# lightMiner.net
KiCad netlist of a schematic drawn in EAGLE
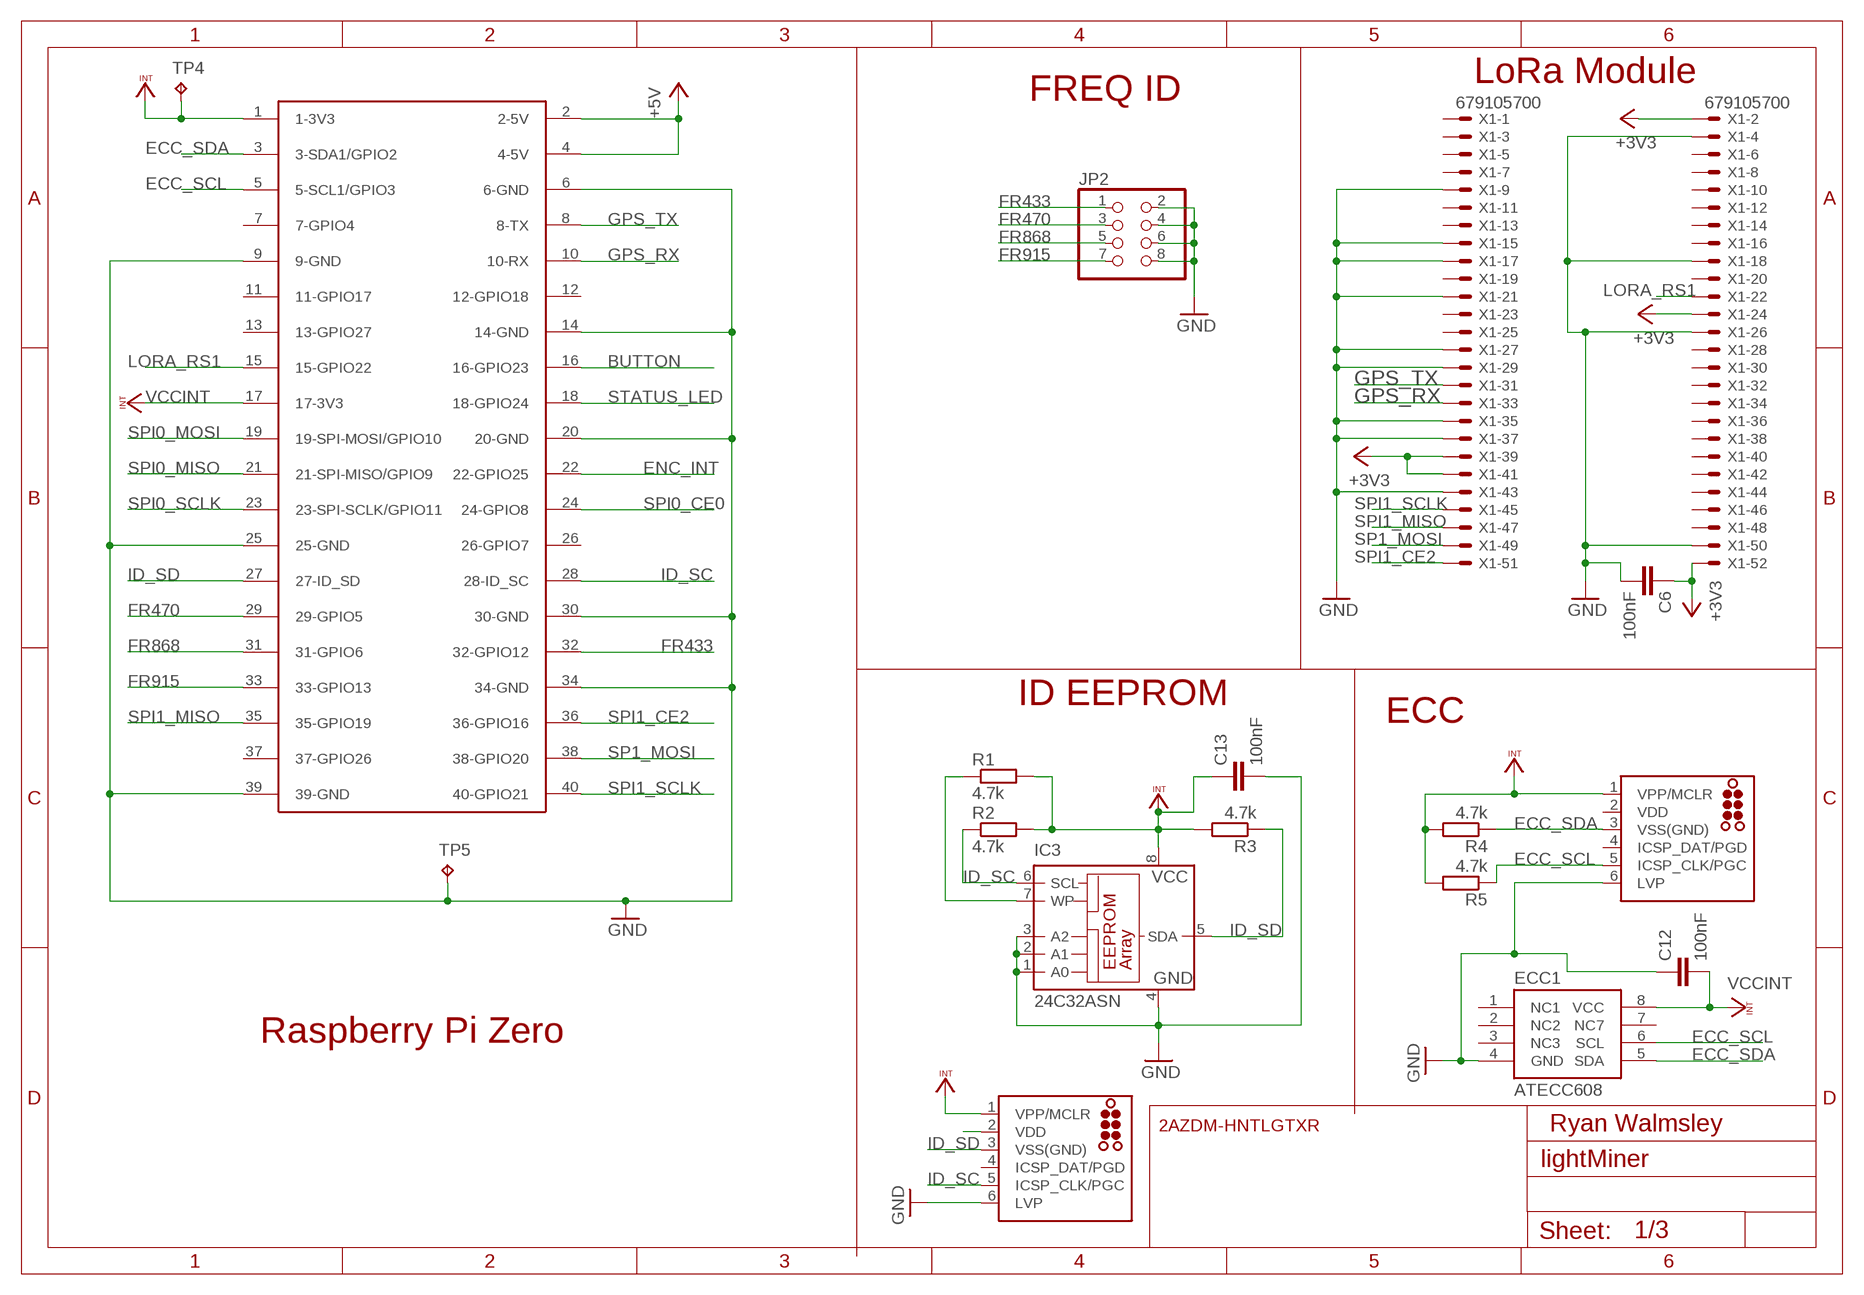
[diagram p0: schematic, sheet 1]
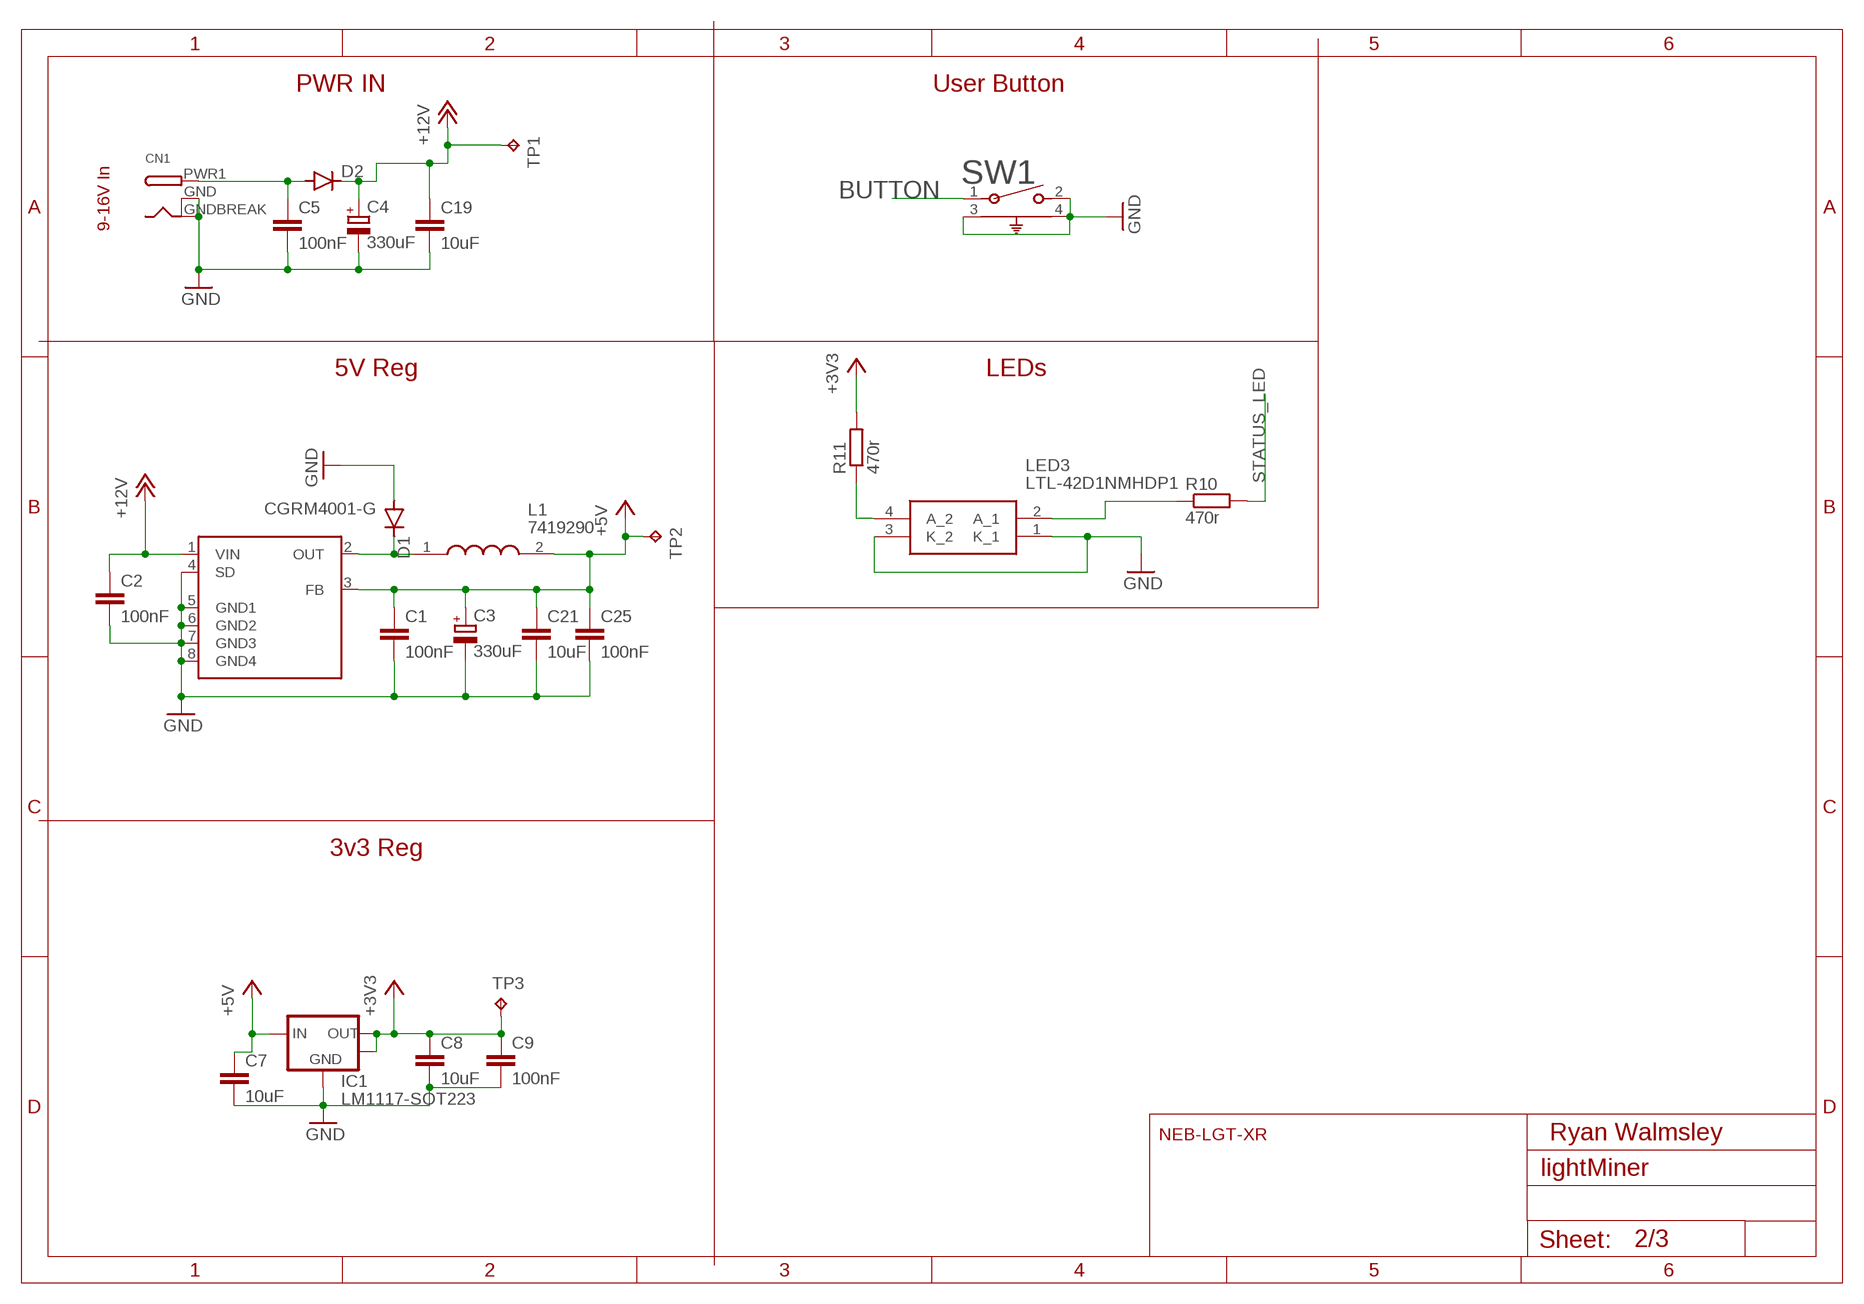
[diagram p1: schematic, sheet 2]
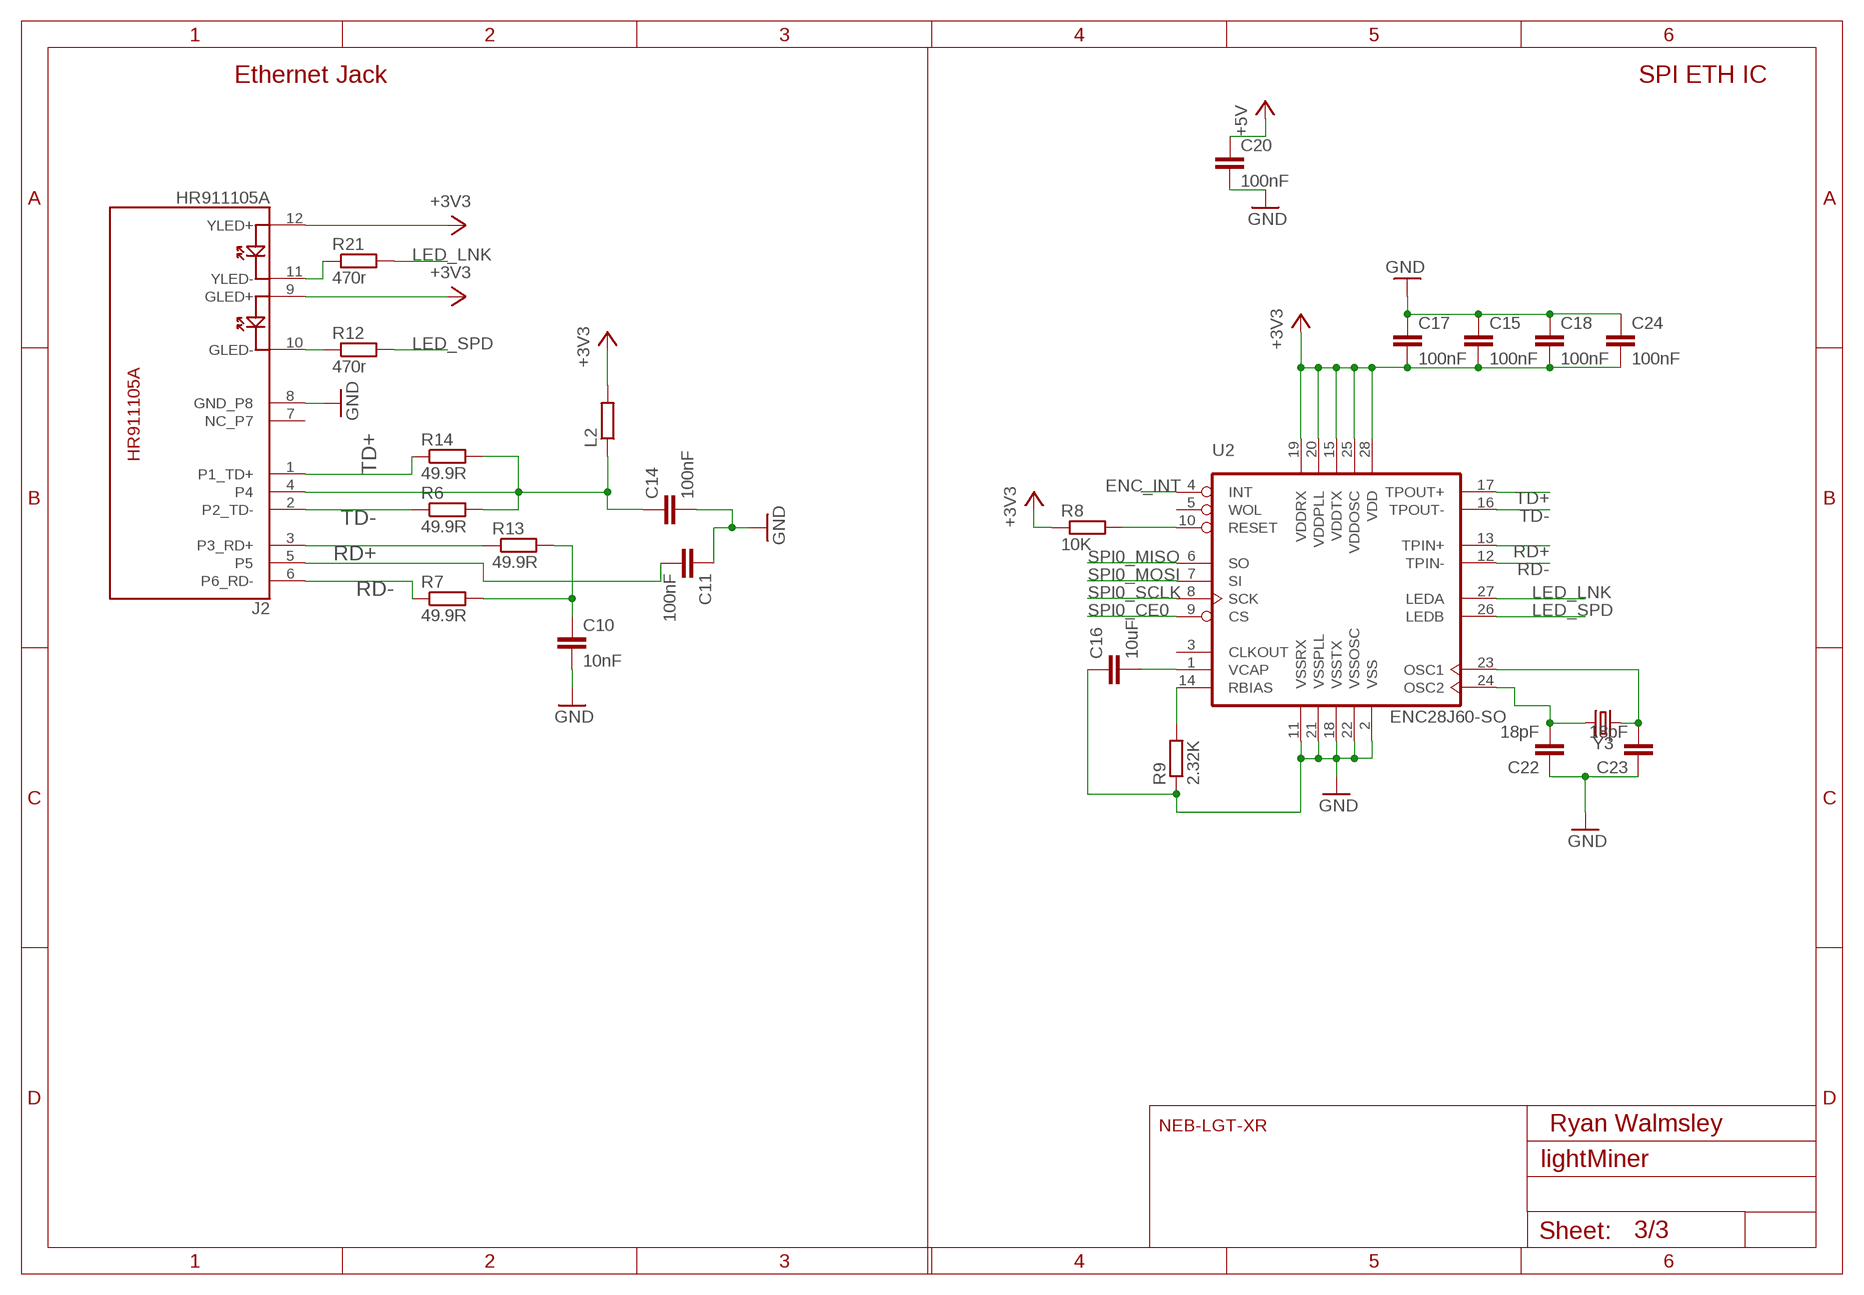
[diagram p2: schematic, sheet 3]

(export (version "E")
  (design (tool "Eeschema 10.0.6"))
  (components
    (comp (ref "C10")
      (value "10nF")
      (footprint "eagle-import:C0603")
      (libsource (lib "eagle-import") (part "C-EUC0603"))
    )
    (comp (ref "C11")
      (value "100nF")
      (footprint "eagle-import:C0603")
      (libsource (lib "eagle-import") (part "C-EUC0603"))
    )
    (comp (ref "C14")
      (value "100nF")
      (footprint "eagle-import:C0603")
      (libsource (lib "eagle-import") (part "C-EUC0603"))
    )
    (comp (ref "C15")
      (value "100nF")
      (footprint "eagle-import:C0603")
      (libsource (lib "eagle-import") (part "C-EUC0603"))
    )
    (comp (ref "C16")
      (value "10uF")
      (footprint "eagle-import:C0805")
      (libsource (lib "eagle-import") (part "C-EUC0805"))
    )
    (comp (ref "C17")
      (value "100nF")
      (footprint "eagle-import:C0603")
      (libsource (lib "eagle-import") (part "C-EUC0603"))
    )
    (comp (ref "C18")
      (value "100nF")
      (footprint "eagle-import:C0603")
      (libsource (lib "eagle-import") (part "C-EUC0603"))
    )
    (comp (ref "C20")
      (value "100nF")
      (footprint "eagle-import:C0603")
      (libsource (lib "eagle-import") (part "C-EUC0603"))
    )
    (comp (ref "C22")
      (value "18pF")
      (footprint "eagle-import:C0603")
      (libsource (lib "eagle-import") (part "C-EUC0603"))
    )
    (comp (ref "C23")
      (value "18pF")
      (footprint "eagle-import:C0603")
      (libsource (lib "eagle-import") (part "C-EUC0603"))
    )
    (comp (ref "C24")
      (value "100nF")
      (footprint "eagle-import:C0603")
      (libsource (lib "eagle-import") (part "C-EUC0603"))
    )
    (comp (ref "J2")
      (value "HR911105A")
      (footprint "eagle-import:HR911105A")
      (libsource (lib "eagle-import") (part "HR911105A"))
    )
    (comp (ref "L2")
      (value "R-EU_R0603")
      (footprint "eagle-import:R0603")
      (libsource (lib "eagle-import") (part "R-EU_R0603"))
    )
    (comp (ref "R6")
      (value "49.9R")
      (footprint "eagle-import:R0603")
      (libsource (lib "eagle-import") (part "R-EU_R0603"))
    )
    (comp (ref "R7")
      (value "49.9R")
      (footprint "eagle-import:R0603")
      (libsource (lib "eagle-import") (part "R-EU_R0603"))
    )
    (comp (ref "R8")
      (value "10K")
      (footprint "eagle-import:R0603")
      (libsource (lib "eagle-import") (part "R-EU_R0603"))
    )
    (comp (ref "R9")
      (value "2.32K")
      (footprint "eagle-import:R0603")
      (libsource (lib "eagle-import") (part "R-EU_R0603"))
    )
    (comp (ref "R12")
      (value "470r")
      (footprint "eagle-import:R0603")
      (libsource (lib "eagle-import") (part "R-EU_R0603"))
    )
    (comp (ref "R13")
      (value "49.9R")
      (footprint "eagle-import:R0603")
      (libsource (lib "eagle-import") (part "R-EU_R0603"))
    )
    (comp (ref "R14")
      (value "49.9R")
      (footprint "eagle-import:R0603")
      (libsource (lib "eagle-import") (part "R-EU_R0603"))
    )
    (comp (ref "R21")
      (value "470r")
      (footprint "eagle-import:R0603")
      (libsource (lib "eagle-import") (part "R-EU_R0603"))
    )
    (comp (ref "U2")
      (value "ENC28J60-SO")
      (footprint "eagle-import:SO28W")
      (libsource (lib "eagle-import") (part "ENC28J60-SO"))
    )
    (comp (ref "Y3")
      (value "25Mhz")
      (footprint "eagle-import:HC49UP")
      (libsource (lib "eagle-import") (part "CRYSTALSMD-HC49UP"))
    )
    (comp (ref "C6")
      (value "100nF")
      (footprint "eagle-import:C0603")
      (libsource (lib "eagle-import") (part "C-EUC0603"))
    )
    (comp (ref "C12")
      (value "100nF")
      (footprint "eagle-import:C0603")
      (libsource (lib "eagle-import") (part "C-EUC0603"))
    )
    (comp (ref "C13")
      (value "100nF")
      (footprint "eagle-import:C0603")
      (libsource (lib "eagle-import") (part "C-EUC0603"))
    )
    (comp (ref "ECC1")
      (value "ATECC608")
      (footprint "eagle-import:SO08")
      (libsource (lib "eagle-import") (part "ATECC108"))
    )
    (comp (ref "IC3")
      (value "24C32ASN")
      (footprint "eagle-import:SO-08")
      (fields (field (name "MPN") "IS24C32A-2GLI"))
      (libsource (lib "eagle-import") (part "24SNC32A"))
    )
    (comp (ref "J1")
      (value "TC2030-MCP-NL")
      (footprint "eagle-import:TC2030-MCP-NL")
      (libsource (lib "eagle-import") (part "TC2030-MCP-NL"))
    )
    (comp (ref "J3")
      (value "TC2030-MCP-NL")
      (footprint "eagle-import:TC2030-MCP-NL")
      (libsource (lib "eagle-import") (part "TC2030-MCP-NL"))
    )
    (comp (ref "JP2")
      (value "PINHD-2X4")
      (footprint "eagle-import:2X04")
      (libsource (lib "eagle-import") (part "PINHD-2X4"))
    )
    (comp (ref "R1")
      (value "4.7k")
      (footprint "eagle-import:R0603")
      (libsource (lib "eagle-import") (part "R-EU_R0603"))
    )
    (comp (ref "R2")
      (value "4.7k")
      (footprint "eagle-import:R0603")
      (libsource (lib "eagle-import") (part "R-EU_R0603"))
    )
    (comp (ref "R3")
      (value "4.7k")
      (footprint "eagle-import:R0603")
      (libsource (lib "eagle-import") (part "R-EU_R0603"))
    )
    (comp (ref "R4")
      (value "4.7k")
      (footprint "eagle-import:R0603")
      (libsource (lib "eagle-import") (part "R-EU_R0603"))
    )
    (comp (ref "R5")
      (value "4.7k")
      (footprint "eagle-import:R0603")
      (libsource (lib "eagle-import") (part "R-EU_R0603"))
    )
    (comp (ref "TP4")
      (value "TPPAD1-13")
      (footprint "eagle-import:P1-13")
      (libsource (lib "eagle-import") (part "TPPAD1-13"))
    )
    (comp (ref "TP5")
      (value "TPPAD1-13")
      (footprint "eagle-import:P1-13")
      (libsource (lib "eagle-import") (part "TPPAD1-13"))
    )
    (comp (ref "U$1")
      (value "RASPBERRY-PI+PIZERO")
      (footprint "eagle-import:RASPBERRY-PI-ZERO")
      (libsource (lib "eagle-import") (part "RASPBERRY-PI+PIZERO"))
    )
    (comp (ref "X1")
      (value "679105700")
      (footprint "eagle-import:679105700")
      (fields (field (name "MPN") "67910-5700"))
      (libsource (lib "eagle-import") (part "679105700"))
    )
    (comp (ref "C1")
      (value "100nF")
      (footprint "eagle-import:C0603")
      (libsource (lib "eagle-import") (part "C-EUC0603"))
    )
    (comp (ref "C2")
      (value "100nF")
      (footprint "eagle-import:C0603")
      (libsource (lib "eagle-import") (part "C-EUC0603"))
    )
    (comp (ref "C3")
      (value "330uF")
      (footprint "eagle-import:E5-10,5")
      (libsource (lib "eagle-import") (part "CPOL-EUE5-10.5"))
    )
    (comp (ref "C4")
      (value "330uF")
      (footprint "eagle-import:E5-10,5")
      (libsource (lib "eagle-import") (part "CPOL-EUE5-10.5"))
    )
    (comp (ref "C5")
      (value "100nF")
      (footprint "eagle-import:C0603")
      (libsource (lib "eagle-import") (part "C-EUC0603"))
    )
    (comp (ref "C7")
      (value "10uF")
      (footprint "eagle-import:C0805")
      (libsource (lib "eagle-import") (part "C-EUC0805"))
    )
    (comp (ref "C8")
      (value "10uF")
      (footprint "eagle-import:C0805")
      (libsource (lib "eagle-import") (part "C-EUC0805"))
    )
    (comp (ref "C9")
      (value "100nF")
      (footprint "eagle-import:C0603")
      (libsource (lib "eagle-import") (part "C-EUC0603"))
    )
    (comp (ref "C19")
      (value "10uF")
      (footprint "eagle-import:C0805")
      (libsource (lib "eagle-import") (part "C-EUC0805"))
    )
    (comp (ref "C21")
      (value "10uF")
      (footprint "eagle-import:C0805")
      (libsource (lib "eagle-import") (part "C-EUC0805"))
    )
    (comp (ref "C25")
      (value "100nF")
      (footprint "eagle-import:C0603")
      (libsource (lib "eagle-import") (part "C-EUC0603"))
    )
    (comp (ref "CN1")
      (value "DCBARRELSMT")
      (footprint "eagle-import:DCJACK_2MM_SMT")
      (libsource (lib "eagle-import") (part "DCBARRELSMT"))
    )
    (comp (ref "D1")
      (value "CGRM4001-G")
      (footprint "eagle-import:SOD-123_MINI-SMA")
      (libsource (lib "eagle-import") (part "CGRM400-G1"))
    )
    (comp (ref "D2")
      (value "DIODE-SMB")
      (footprint "eagle-import:SMB")
      (libsource (lib "eagle-import") (part "DIODE-SMB"))
    )
    (comp (ref "IC1")
      (value "LM1117-SOT223")
      (footprint "eagle-import:SOT-223-3")
      (libsource (lib "eagle-import") (part "LM1117-SOT223"))
    )
    (comp (ref "L1")
      (value "7419290")
      (footprint "eagle-import:INDPM115100X410N")
      (libsource (lib "eagle-import") (part "7419290"))
    )
    (comp (ref "LED3")
      (value "LTL-42D1NMHDP1")
      (footprint "eagle-import:LTL42D1NMHDP1")
      (fields (field (name "MOUSER_PART_NUMBER") "859-LTL-42D1NMHDP1"))
      (libsource (lib "eagle-import") (part "LTL-42D1NMHDP1"))
    )
    (comp (ref "R10")
      (value "470r")
      (footprint "eagle-import:R0603")
      (libsource (lib "eagle-import") (part "R-EU_R0603"))
    )
    (comp (ref "R11")
      (value "470r")
      (footprint "eagle-import:R0603")
      (libsource (lib "eagle-import") (part "R-EU_R0603"))
    )
    (comp (ref "SW1")
      (value "1825027-8")
      (footprint "eagle-import:SW2_1825027-C_TEC")
      (fields (field (name "COPYRIGHT") "Copyright (C) 2016 Accelerated Designs. All rights reserved"))
      (libsource (lib "eagle-import") (part "1825027-8"))
    )
    (comp (ref "TP1")
      (value "TPPAD1-13")
      (footprint "eagle-import:P1-13")
      (libsource (lib "eagle-import") (part "TPPAD1-13"))
    )
    (comp (ref "TP2")
      (value "TPPAD1-13")
      (footprint "eagle-import:P1-13")
      (libsource (lib "eagle-import") (part "TPPAD1-13"))
    )
    (comp (ref "TP3")
      (value "TPPAD1-13")
      (footprint "eagle-import:P1-13")
      (libsource (lib "eagle-import") (part "TPPAD1-13"))
    )
    (comp (ref "U1")
      (value "AP1509")
      (footprint "eagle-import:SO08")
      (libsource (lib "eagle-import") (part "AP1509"))
    )
  )
  (nets
    (net (code "1") (name "+3V3") (class "Default")
      (node (ref "C15") (pin "2") (pinfunction "2_2") (pintype "passive"))
      (node (ref "C17") (pin "2") (pinfunction "2_2") (pintype "passive"))
      (node (ref "C18") (pin "2") (pinfunction "2_2") (pintype "passive"))
      (node (ref "C24") (pin "2") (pinfunction "2_2") (pintype "passive"))
      (node (ref "C6") (pin "1") (pinfunction "1_1") (pintype "passive"))
      (node (ref "C8") (pin "1") (pinfunction "1_1") (pintype "passive"))
      (node (ref "C9") (pin "1") (pinfunction "1_1") (pintype "passive"))
      (node (ref "IC1") (pin "2") (pinfunction "VOUT_2") (pintype "bidirectional"))
      (node (ref "IC1") (pin "4") (pinfunction "HEATSINK_4") (pintype "bidirectional"))
      (node (ref "J2") (pin "12") (pinfunction "YLED+_12") (pintype "bidirectional"))
      (node (ref "J2") (pin "9") (pinfunction "GLED+_9") (pintype "bidirectional"))
      (node (ref "L2") (pin "2") (pinfunction "2_2") (pintype "passive"))
      (node (ref "R11") (pin "2") (pinfunction "2_2") (pintype "passive"))
      (node (ref "R8") (pin "1") (pinfunction "1_1") (pintype "passive"))
      (node (ref "TP3") (pin "TP") (pinfunction "TP_TP") (pintype "input"))
      (node (ref "U2") (pin "15") (pinfunction "VDDTX_15") (pintype "power_in"))
      (node (ref "U2") (pin "19") (pinfunction "VDDRX_19") (pintype "power_in"))
      (node (ref "U2") (pin "20") (pinfunction "VDDPLL_20") (pintype "power_in"))
      (node (ref "U2") (pin "25") (pinfunction "VDDOSC_25") (pintype "power_in"))
      (node (ref "U2") (pin "28") (pinfunction "VDD_28") (pintype "power_in"))
      (node (ref "X1") (pin "2") (pinfunction "S_2") (pintype "passive"))
      (node (ref "X1") (pin "24") (pinfunction "S_24") (pintype "passive"))
      (node (ref "X1") (pin "39") (pinfunction "S_39") (pintype "passive"))
      (node (ref "X1") (pin "41") (pinfunction "S_41") (pintype "passive"))
      (node (ref "X1") (pin "52") (pinfunction "S_52") (pintype "passive"))
    )
    (net (code "2") (name "+5V") (class "Default")
      (node (ref "C1") (pin "1") (pinfunction "1_1") (pintype "passive"))
      (node (ref "C20") (pin "1") (pinfunction "1_1") (pintype "passive"))
      (node (ref "C21") (pin "1") (pinfunction "1_1") (pintype "passive"))
      (node (ref "C25") (pin "1") (pinfunction "1_1") (pintype "passive"))
      (node (ref "C3") (pin "+") (pinfunction "+_+") (pintype "passive"))
      (node (ref "C7") (pin "1") (pinfunction "1_1") (pintype "passive"))
      (node (ref "IC1") (pin "3") (pinfunction "VIN_3") (pintype "bidirectional"))
      (node (ref "L1") (pin "2") (pinfunction "2_2") (pintype "bidirectional"))
      (node (ref "TP2") (pin "TP") (pinfunction "TP_TP") (pintype "input"))
      (node (ref "U$1") (pin "2") (pinfunction "2-5V_2") (pintype "bidirectional"))
      (node (ref "U$1") (pin "4") (pinfunction "4-5V_4") (pintype "bidirectional"))
      (node (ref "U1") (pin "3") (pinfunction "FB_3") (pintype "input"))
    )
    (net (code "3") (name "+12V") (class "Default")
      (node (ref "C19") (pin "1") (pinfunction "1_1") (pintype "passive"))
      (node (ref "C2") (pin "1") (pinfunction "1_1") (pintype "passive"))
      (node (ref "C4") (pin "+") (pinfunction "+_+") (pintype "passive"))
      (node (ref "D2") (pin "C") (pinfunction "C_C") (pintype "passive"))
      (node (ref "TP1") (pin "TP") (pinfunction "TP_TP") (pintype "input"))
      (node (ref "U1") (pin "1") (pinfunction "VIN_1") (pintype "power_in"))
    )
    (net (code "4") (name "BUTTON") (class "Default")
      (node (ref "SW1") (pin "1") (pinfunction "1_1") (pintype "passive"))
      (node (ref "U$1") (pin "16") (pinfunction "16-GPIO23_16") (pintype "bidirectional"))
    )
    (net (code "5") (name "ECC_SCL") (class "Default")
      (node (ref "ECC1") (pin "6") (pinfunction "SCL_6") (pintype "bidirectional"))
      (node (ref "J1") (pin "5") (pinfunction "ICSP_CLK/PGC_5") (pintype "output"))
      (node (ref "R5") (pin "1") (pinfunction "1_1") (pintype "passive"))
      (node (ref "U$1") (pin "5") (pinfunction "5-SCL1/GPIO3_5") (pintype "bidirectional"))
    )
    (net (code "6") (name "ECC_SDA") (class "Default")
      (node (ref "ECC1") (pin "5") (pinfunction "SDA_5") (pintype "bidirectional"))
      (node (ref "J1") (pin "3") (pinfunction "VSS(GND)_3") (pintype "power_in"))
      (node (ref "R4") (pin "1") (pinfunction "1_1") (pintype "passive"))
      (node (ref "U$1") (pin "3") (pinfunction "3-SDA1/GPIO2_3") (pintype "bidirectional"))
    )
    (net (code "7") (name "ENC_INT") (class "Default")
      (node (ref "U$1") (pin "22") (pinfunction "22-GPIO25_22") (pintype "bidirectional"))
      (node (ref "U2") (pin "4") (pinfunction "INT_4") (pintype "output"))
    )
    (net (code "8") (name "FR433") (class "Default")
      (node (ref "JP2") (pin "1") (pinfunction "1_1") (pintype "passive"))
      (node (ref "U$1") (pin "32") (pinfunction "32-GPIO12_32") (pintype "bidirectional"))
    )
    (net (code "9") (name "FR470") (class "Default")
      (node (ref "JP2") (pin "3") (pinfunction "3_3") (pintype "passive"))
      (node (ref "U$1") (pin "29") (pinfunction "29-GPIO5_29") (pintype "bidirectional"))
    )
    (net (code "10") (name "FR868") (class "Default")
      (node (ref "JP2") (pin "5") (pinfunction "5_5") (pintype "passive"))
      (node (ref "U$1") (pin "31") (pinfunction "31-GPIO6_31") (pintype "bidirectional"))
    )
    (net (code "11") (name "FR915") (class "Default")
      (node (ref "JP2") (pin "7") (pinfunction "7_7") (pintype "passive"))
      (node (ref "U$1") (pin "33") (pinfunction "33-GPIO13_33") (pintype "bidirectional"))
    )
    (net (code "12") (name "GND") (class "Default")
      (node (ref "C1") (pin "2") (pinfunction "2_2") (pintype "passive"))
      (node (ref "C10") (pin "2") (pinfunction "2_2") (pintype "passive"))
      (node (ref "C11") (pin "1") (pinfunction "1_1") (pintype "passive"))
      (node (ref "C12") (pin "1") (pinfunction "1_1") (pintype "passive"))
      (node (ref "C13") (pin "2") (pinfunction "2_2") (pintype "passive"))
      (node (ref "C14") (pin "2") (pinfunction "2_2") (pintype "passive"))
      (node (ref "C15") (pin "1") (pinfunction "1_1") (pintype "passive"))
      (node (ref "C16") (pin "1") (pinfunction "1_1") (pintype "passive"))
      (node (ref "C17") (pin "1") (pinfunction "1_1") (pintype "passive"))
      (node (ref "C18") (pin "1") (pinfunction "1_1") (pintype "passive"))
      (node (ref "C19") (pin "2") (pinfunction "2_2") (pintype "passive"))
      (node (ref "C2") (pin "2") (pinfunction "2_2") (pintype "passive"))
      (node (ref "C20") (pin "2") (pinfunction "2_2") (pintype "passive"))
      (node (ref "C21") (pin "2") (pinfunction "2_2") (pintype "passive"))
      (node (ref "C22") (pin "1") (pinfunction "1_1") (pintype "passive"))
      (node (ref "C23") (pin "1") (pinfunction "1_1") (pintype "passive"))
      (node (ref "C24") (pin "1") (pinfunction "1_1") (pintype "passive"))
      (node (ref "C25") (pin "2") (pinfunction "2_2") (pintype "passive"))
      (node (ref "C3") (pin "-") (pinfunction "-_-") (pintype "passive"))
      (node (ref "C4") (pin "-") (pinfunction "-_-") (pintype "passive"))
      (node (ref "C5") (pin "2") (pinfunction "2_2") (pintype "passive"))
      (node (ref "C6") (pin "2") (pinfunction "2_2") (pintype "passive"))
      (node (ref "C7") (pin "2") (pinfunction "2_2") (pintype "passive"))
      (node (ref "C8") (pin "2") (pinfunction "2_2") (pintype "passive"))
      (node (ref "C9") (pin "2") (pinfunction "2_2") (pintype "passive"))
      (node (ref "CN1") (pin "GND") (pinfunction "GNDBREAK_GND") (pintype "power_in"))
      (node (ref "CN1") (pin "GNDBREAK") (pinfunction "GND_GNDBREAK") (pintype "power_in"))
      (node (ref "D1") (pin "A") (pinfunction "A_A") (pintype "passive"))
      (node (ref "ECC1") (pin "4") (pinfunction "GND_4") (pintype "power_in"))
      (node (ref "IC1") (pin "1") (pinfunction "GND_1") (pintype "bidirectional"))
      (node (ref "IC3") (pin "1") (pinfunction "A0_1") (pintype "input"))
      (node (ref "IC3") (pin "2") (pinfunction "A1_2") (pintype "input"))
      (node (ref "IC3") (pin "3") (pinfunction "A2_3") (pintype "input"))
      (node (ref "IC3") (pin "4") (pinfunction "GND_4") (pintype "power_in"))
      (node (ref "J1") (pin "6") (pinfunction "LVP_6") (pintype "bidirectional"))
      (node (ref "J2") (pin "8") (pinfunction "GND_P8_8") (pintype "bidirectional"))
      (node (ref "J3") (pin "6") (pinfunction "LVP_6") (pintype "bidirectional"))
      (node (ref "JP2") (pin "2") (pinfunction "2_2") (pintype "passive"))
      (node (ref "JP2") (pin "4") (pinfunction "4_4") (pintype "passive"))
      (node (ref "JP2") (pin "6") (pinfunction "6_6") (pintype "passive"))
      (node (ref "JP2") (pin "8") (pinfunction "8_8") (pintype "passive"))
      (node (ref "LED3") (pin "1") (pinfunction "K_1_1") (pintype "bidirectional"))
      (node (ref "LED3") (pin "3") (pinfunction "K_2_3") (pintype "bidirectional"))
      (node (ref "R9") (pin "1") (pinfunction "1_1") (pintype "passive"))
      (node (ref "SW1") (pin "2") (pinfunction "2_2") (pintype "passive"))
      (node (ref "SW1") (pin "3") (pinfunction "3_3") (pintype "passive"))
      (node (ref "SW1") (pin "4") (pinfunction "4_4") (pintype "passive"))
      (node (ref "TP5") (pin "TP") (pinfunction "TP_TP") (pintype "input"))
      (node (ref "U$1") (pin "14") (pinfunction "14-GND_14") (pintype "bidirectional"))
      (node (ref "U$1") (pin "20") (pinfunction "20-GND_20") (pintype "bidirectional"))
      (node (ref "U$1") (pin "25") (pinfunction "25-GND_25") (pintype "bidirectional"))
      (node (ref "U$1") (pin "30") (pinfunction "30-GND_30") (pintype "bidirectional"))
      (node (ref "U$1") (pin "34") (pinfunction "34-GND_34") (pintype "bidirectional"))
      (node (ref "U$1") (pin "39") (pinfunction "39-GND_39") (pintype "bidirectional"))
      (node (ref "U$1") (pin "6") (pinfunction "6-GND_6") (pintype "bidirectional"))
      (node (ref "U$1") (pin "9") (pinfunction "9-GND_9") (pintype "bidirectional"))
      (node (ref "U1") (pin "4") (pinfunction "SD_4") (pintype "input"))
      (node (ref "U1") (pin "5") (pinfunction "GND1_5") (pintype "power_in"))
      (node (ref "U1") (pin "6") (pinfunction "GND2_6") (pintype "power_in"))
      (node (ref "U1") (pin "7") (pinfunction "GND3_7") (pintype "power_in"))
      (node (ref "U1") (pin "8") (pinfunction "GND4_8") (pintype "power_in"))
      (node (ref "U2") (pin "11") (pinfunction "VSSRX_11") (pintype "power_in"))
      (node (ref "U2") (pin "18") (pinfunction "VSSTX_18") (pintype "power_in"))
      (node (ref "U2") (pin "2") (pinfunction "VSS_2") (pintype "power_in"))
      (node (ref "U2") (pin "21") (pinfunction "VSSPLL_21") (pintype "power_in"))
      (node (ref "U2") (pin "22") (pinfunction "VSSOSC_22") (pintype "power_in"))
      (node (ref "X1") (pin "15") (pinfunction "S_15") (pintype "passive"))
      (node (ref "X1") (pin "17") (pinfunction "S_17") (pintype "passive"))
      (node (ref "X1") (pin "18") (pinfunction "S_18") (pintype "passive"))
      (node (ref "X1") (pin "21") (pinfunction "S_21") (pintype "passive"))
      (node (ref "X1") (pin "26") (pinfunction "S_26") (pintype "passive"))
      (node (ref "X1") (pin "27") (pinfunction "S_27") (pintype "passive"))
      (node (ref "X1") (pin "29") (pinfunction "S_29") (pintype "passive"))
      (node (ref "X1") (pin "35") (pinfunction "S_35") (pintype "passive"))
      (node (ref "X1") (pin "37") (pinfunction "S_37") (pintype "passive"))
      (node (ref "X1") (pin "4") (pinfunction "S_4") (pintype "passive"))
      (node (ref "X1") (pin "43") (pinfunction "S_43") (pintype "passive"))
      (node (ref "X1") (pin "50") (pinfunction "S_50") (pintype "passive"))
      (node (ref "X1") (pin "9") (pinfunction "S_9") (pintype "passive"))
    )
    (net (code "13") (name "GPS_RX") (class "Default")
      (node (ref "U$1") (pin "10") (pinfunction "10-RX_10") (pintype "bidirectional"))
      (node (ref "X1") (pin "33") (pinfunction "S_33") (pintype "passive"))
    )
    (net (code "14") (name "GPS_TX") (class "Default")
      (node (ref "U$1") (pin "8") (pinfunction "8-TX_8") (pintype "bidirectional"))
      (node (ref "X1") (pin "31") (pinfunction "S_31") (pintype "passive"))
    )
    (net (code "15") (name "ID_SC") (class "Default")
      (node (ref "IC3") (pin "6") (pinfunction "SCL_6") (pintype "input"))
      (node (ref "J3") (pin "5") (pinfunction "ICSP_CLK/PGC_5") (pintype "output"))
      (node (ref "R2") (pin "1") (pinfunction "1_1") (pintype "passive"))
      (node (ref "U$1") (pin "28") (pinfunction "28-ID_SC_28") (pintype "bidirectional"))
    )
    (net (code "16") (name "ID_SD") (class "Default")
      (node (ref "IC3") (pin "5") (pinfunction "SDA_5") (pintype "bidirectional"))
      (node (ref "J3") (pin "3") (pinfunction "VSS(GND)_3") (pintype "power_in"))
      (node (ref "R3") (pin "1") (pinfunction "1_1") (pintype "passive"))
      (node (ref "U$1") (pin "27") (pinfunction "27-ID_SD_27") (pintype "bidirectional"))
    )
    (net (code "17") (name "LED_LNK") (class "Default")
      (node (ref "R21") (pin "2") (pinfunction "2_2") (pintype "passive"))
      (node (ref "U2") (pin "27") (pinfunction "LEDA_27") (pintype "output"))
    )
    (net (code "18") (name "LED_SPD") (class "Default")
      (node (ref "R12") (pin "2") (pinfunction "2_2") (pintype "passive"))
      (node (ref "U2") (pin "26") (pinfunction "LEDB_26") (pintype "output"))
    )
    (net (code "19") (name "LORA_RS1") (class "Default")
      (node (ref "U$1") (pin "15") (pinfunction "15-GPIO22_15") (pintype "bidirectional"))
      (node (ref "X1") (pin "22") (pinfunction "S_22") (pintype "passive"))
    )
    (net (code "20") (name "Net-(C10-Pad1)") (class "Default")
      (node (ref "C10") (pin "1") (pinfunction "1_1") (pintype "passive"))
      (node (ref "R13") (pin "2") (pinfunction "2_2") (pintype "passive"))
      (node (ref "R7") (pin "2") (pinfunction "2_2") (pintype "passive"))
    )
    (net (code "21") (name "Net-(CN1-PWR)") (class "Default")
      (node (ref "C5") (pin "1") (pinfunction "1_1") (pintype "passive"))
      (node (ref "CN1") (pin "PWR1") (pinfunction "PWR_PWR1") (pintype "power_in"))
      (node (ref "D2") (pin "A") (pinfunction "A_A") (pintype "passive"))
    )
    (net (code "22") (name "Net-(IC3-WP)") (class "Default")
      (node (ref "IC3") (pin "7") (pinfunction "WP_7") (pintype "input"))
      (node (ref "R1") (pin "1") (pinfunction "1_1") (pintype "passive"))
    )
    (net (code "23") (name "Net-(J2-GLED-)") (class "Default")
      (node (ref "J2") (pin "10") (pinfunction "GLED-_10") (pintype "bidirectional"))
      (node (ref "R12") (pin "1") (pinfunction "1_1") (pintype "passive"))
    )
    (net (code "24") (name "Net-(J2-P4)") (class "Default")
      (node (ref "C14") (pin "1") (pinfunction "1_1") (pintype "passive"))
      (node (ref "J2") (pin "4") (pinfunction "P4_4") (pintype "bidirectional"))
      (node (ref "L2") (pin "1") (pinfunction "1_1") (pintype "passive"))
      (node (ref "R14") (pin "2") (pinfunction "2_2") (pintype "passive"))
      (node (ref "R6") (pin "2") (pinfunction "2_2") (pintype "passive"))
    )
    (net (code "25") (name "Net-(J2-P5)") (class "Default")
      (node (ref "C11") (pin "2") (pinfunction "2_2") (pintype "passive"))
      (node (ref "J2") (pin "5") (pinfunction "P5_5") (pintype "bidirectional"))
    )
    (net (code "26") (name "Net-(J2-YLED-)") (class "Default")
      (node (ref "J2") (pin "11") (pinfunction "YLED-_11") (pintype "bidirectional"))
      (node (ref "R21") (pin "1") (pinfunction "1_1") (pintype "passive"))
    )
    (net (code "27") (name "Net-(LED3-A_1)") (class "Default")
      (node (ref "LED3") (pin "2") (pinfunction "A_1_2") (pintype "bidirectional"))
      (node (ref "R10") (pin "1") (pinfunction "1_1") (pintype "passive"))
    )
    (net (code "28") (name "Net-(LED3-A_2)") (class "Default")
      (node (ref "LED3") (pin "4") (pinfunction "A_2_4") (pintype "bidirectional"))
      (node (ref "R11") (pin "1") (pinfunction "1_1") (pintype "passive"))
    )
    (net (code "29") (name "Net-(U1-OUT)") (class "Default")
      (node (ref "D1") (pin "C") (pinfunction "C_C") (pintype "passive"))
      (node (ref "L1") (pin "1") (pinfunction "1_1") (pintype "bidirectional"))
      (node (ref "U1") (pin "2") (pinfunction "OUT_2") (pintype "output"))
    )
    (net (code "30") (name "Net-(U2-OSC1)") (class "Default")
      (node (ref "C23") (pin "2") (pinfunction "2_2") (pintype "passive"))
      (node (ref "U2") (pin "23") (pinfunction "OSC1_23") (pintype "input"))
      (node (ref "Y3") (pin "1") (pinfunction "1_1") (pintype "passive"))
    )
    (net (code "31") (name "Net-(U2-OSC2)") (class "Default")
      (node (ref "C22") (pin "2") (pinfunction "2_2") (pintype "passive"))
      (node (ref "U2") (pin "24") (pinfunction "OSC2_24") (pintype "output"))
      (node (ref "Y3") (pin "2") (pinfunction "2_2") (pintype "passive"))
    )
    (net (code "32") (name "Net-(U2-RBIAS)") (class "Default")
      (node (ref "R9") (pin "2") (pinfunction "2_2") (pintype "passive"))
      (node (ref "U2") (pin "14") (pinfunction "RBIAS_14") (pintype "passive"))
    )
    (net (code "33") (name "Net-(U2-RESET)") (class "Default")
      (node (ref "R8") (pin "2") (pinfunction "2_2") (pintype "passive"))
      (node (ref "U2") (pin "10") (pinfunction "RESET_10") (pintype "input"))
    )
    (net (code "34") (name "Net-(U2-VCAP)") (class "Default")
      (node (ref "C16") (pin "2") (pinfunction "2_2") (pintype "passive"))
      (node (ref "U2") (pin "1") (pinfunction "VCAP_1") (pintype "power_in"))
    )
    (net (code "35") (name "RD+") (class "Default")
      (node (ref "J2") (pin "3") (pinfunction "P3_RD+_3") (pintype "bidirectional"))
      (node (ref "R13") (pin "1") (pinfunction "1_1") (pintype "passive"))
      (node (ref "U2") (pin "13") (pinfunction "TPIN+_13") (pintype "input"))
    )
    (net (code "36") (name "RD-") (class "Default")
      (node (ref "J2") (pin "6") (pinfunction "P6_RD-_6") (pintype "bidirectional"))
      (node (ref "R7") (pin "1") (pinfunction "1_1") (pintype "passive"))
      (node (ref "U2") (pin "12") (pinfunction "TPIN-_12") (pintype "input"))
    )
    (net (code "37") (name "SP1_MOSI") (class "Default")
      (node (ref "U$1") (pin "38") (pinfunction "38-GPIO20_38") (pintype "bidirectional"))
      (node (ref "X1") (pin "49") (pinfunction "S_49") (pintype "passive"))
    )
    (net (code "38") (name "SPI0_CE0") (class "Default")
      (node (ref "U$1") (pin "24") (pinfunction "24-GPIO8_24") (pintype "bidirectional"))
      (node (ref "U2") (pin "9") (pinfunction "CS_9") (pintype "input"))
    )
    (net (code "39") (name "SPI0_MISO") (class "Default")
      (node (ref "U$1") (pin "21") (pinfunction "21-SPI-MISO/GPIO9_21") (pintype "bidirectional"))
      (node (ref "U2") (pin "6") (pinfunction "SO_6") (pintype "output"))
    )
    (net (code "40") (name "SPI0_MOSI") (class "Default")
      (node (ref "U$1") (pin "19") (pinfunction "19-SPI-MOSI/GPIO10_19") (pintype "bidirectional"))
      (node (ref "U2") (pin "7") (pinfunction "SI_7") (pintype "input"))
    )
    (net (code "41") (name "SPI0_SCLK") (class "Default")
      (node (ref "U$1") (pin "23") (pinfunction "23-SPI-SCLK/GPIO11_23") (pintype "bidirectional"))
      (node (ref "U2") (pin "8") (pinfunction "SCK_8") (pintype "input"))
    )
    (net (code "42") (name "SPI1_CE2") (class "Default")
      (node (ref "U$1") (pin "36") (pinfunction "36-GPIO16_36") (pintype "bidirectional"))
      (node (ref "X1") (pin "51") (pinfunction "S_51") (pintype "passive"))
    )
    (net (code "43") (name "SPI1_MISO") (class "Default")
      (node (ref "U$1") (pin "35") (pinfunction "35-GPIO19_35") (pintype "bidirectional"))
      (node (ref "X1") (pin "47") (pinfunction "S_47") (pintype "passive"))
    )
    (net (code "44") (name "SPI1_SCLK") (class "Default")
      (node (ref "U$1") (pin "40") (pinfunction "40-GPIO21_40") (pintype "bidirectional"))
      (node (ref "X1") (pin "45") (pinfunction "S_45") (pintype "passive"))
    )
    (net (code "45") (name "STATUS_LED") (class "Default")
      (node (ref "R10") (pin "2") (pinfunction "2_2") (pintype "passive"))
      (node (ref "U$1") (pin "18") (pinfunction "18-GPIO24_18") (pintype "bidirectional"))
    )
    (net (code "46") (name "TD+") (class "Default")
      (node (ref "J2") (pin "1") (pinfunction "P1_TD+_1") (pintype "bidirectional"))
      (node (ref "R14") (pin "1") (pinfunction "1_1") (pintype "passive"))
      (node (ref "U2") (pin "17") (pinfunction "TPOUT+_17") (pintype "output"))
    )
    (net (code "47") (name "TD-") (class "Default")
      (node (ref "J2") (pin "2") (pinfunction "P2_TD-_2") (pintype "bidirectional"))
      (node (ref "R6") (pin "1") (pinfunction "1_1") (pintype "passive"))
      (node (ref "U2") (pin "16") (pinfunction "TPOUT-_16") (pintype "output"))
    )
    (net (code "48") (name "VCCINT") (class "Default")
      (node (ref "C12") (pin "2") (pinfunction "2_2") (pintype "passive"))
      (node (ref "C13") (pin "1") (pinfunction "1_1") (pintype "passive"))
      (node (ref "ECC1") (pin "8") (pinfunction "VCC_8") (pintype "power_in"))
      (node (ref "IC3") (pin "8") (pinfunction "VCC_8") (pintype "power_in"))
      (node (ref "J1") (pin "1") (pinfunction "VPP/MCLR_1") (pintype "passive"))
      (node (ref "J3") (pin "1") (pinfunction "VPP/MCLR_1") (pintype "passive"))
      (node (ref "R1") (pin "2") (pinfunction "2_2") (pintype "passive"))
      (node (ref "R2") (pin "2") (pinfunction "2_2") (pintype "passive"))
      (node (ref "R3") (pin "2") (pinfunction "2_2") (pintype "passive"))
      (node (ref "R4") (pin "2") (pinfunction "2_2") (pintype "passive"))
      (node (ref "R5") (pin "2") (pinfunction "2_2") (pintype "passive"))
      (node (ref "TP4") (pin "TP") (pinfunction "TP_TP") (pintype "input"))
      (node (ref "U$1") (pin "1") (pinfunction "1-3V3_1") (pintype "bidirectional"))
      (node (ref "U$1") (pin "17") (pinfunction "17-3V3_17") (pintype "bidirectional"))
    )
    (net (code "49") (name "VDD") (class "Default")
      (node (ref "J1") (pin "2") (pinfunction "VDD_2") (pintype "power_in"))
    )
    (net (code "50") (name "unconnected-(ECC1-NC1-Pad1)") (class "Default")
      (node (ref "ECC1") (pin "1") (pinfunction "NC1_1") (pintype "bidirectional"))
    )
    (net (code "51") (name "unconnected-(ECC1-NC2-Pad2)") (class "Default")
      (node (ref "ECC1") (pin "2") (pinfunction "NC2_2") (pintype "no_connect"))
    )
    (net (code "52") (name "unconnected-(ECC1-NC3-Pad3)") (class "Default")
      (node (ref "ECC1") (pin "3") (pinfunction "NC3_3") (pintype "no_connect"))
    )
    (net (code "53") (name "unconnected-(ECC1-NC7-Pad7)") (class "Default")
      (node (ref "ECC1") (pin "7") (pinfunction "NC7_7") (pintype "no_connect"))
    )
    (net (code "54") (name "unconnected-(J1-ICSP_DAT{slash}PGD-Pad4)") (class "Default")
      (node (ref "J1") (pin "4") (pinfunction "ICSP_DAT/PGD_4") (pintype "bidirectional"))
    )
    (net (code "55") (name "unconnected-(J2-NC_P7-Pad7)") (class "Default")
      (node (ref "J2") (pin "7") (pinfunction "NC_P7_7") (pintype "bidirectional"))
    )
    (net (code "56") (name "unconnected-(J3-ICSP_DAT{slash}PGD-Pad4)") (class "Default")
      (node (ref "J3") (pin "4") (pinfunction "ICSP_DAT/PGD_4") (pintype "bidirectional"))
    )
    (net (code "57") (name "unconnected-(J3-VDD-Pad2)") (class "Default")
      (node (ref "J3") (pin "2") (pinfunction "VDD_2") (pintype "power_in"))
    )
    (net (code "58") (name "unconnected-(U$1-7-GPIO4-Pad7)") (class "Default")
      (node (ref "U$1") (pin "7") (pinfunction "7-GPIO4_7") (pintype "bidirectional"))
    )
    (net (code "59") (name "unconnected-(U$1-11-GPIO17-Pad11)") (class "Default")
      (node (ref "U$1") (pin "11") (pinfunction "11-GPIO17_11") (pintype "bidirectional"))
    )
    (net (code "60") (name "unconnected-(U$1-12-GPIO18-Pad12)") (class "Default")
      (node (ref "U$1") (pin "12") (pinfunction "12-GPIO18_12") (pintype "bidirectional"))
    )
    (net (code "61") (name "unconnected-(U$1-13-GPIO27-Pad13)") (class "Default")
      (node (ref "U$1") (pin "13") (pinfunction "13-GPIO27_13") (pintype "bidirectional"))
    )
    (net (code "62") (name "unconnected-(U$1-26-GPIO7-Pad26)") (class "Default")
      (node (ref "U$1") (pin "26") (pinfunction "26-GPIO7_26") (pintype "bidirectional"))
    )
    (net (code "63") (name "unconnected-(U$1-37-GPIO26-Pad37)") (class "Default")
      (node (ref "U$1") (pin "37") (pinfunction "37-GPIO26_37") (pintype "bidirectional"))
    )
    (net (code "64") (name "unconnected-(U2-CLKOUT-Pad3)") (class "Default")
      (node (ref "U2") (pin "3") (pinfunction "CLKOUT_3") (pintype "output"))
    )
    (net (code "65") (name "unconnected-(U2-WOL-Pad5)") (class "Default")
      (node (ref "U2") (pin "5") (pinfunction "WOL_5") (pintype "output"))
    )
    (net (code "66") (name "unconnected-(X1A-S-Pad1)") (class "Default")
      (node (ref "X1") (pin "1") (pinfunction "S_1") (pintype "passive"))
    )
    (net (code "67") (name "unconnected-(X1AB-S-Pad34)") (class "Default")
      (node (ref "X1") (pin "34") (pinfunction "S_34") (pintype "passive"))
    )
    (net (code "68") (name "unconnected-(X1AD-S-Pad36)") (class "Default")
      (node (ref "X1") (pin "36") (pinfunction "S_36") (pintype "passive"))
    )
    (net (code "69") (name "unconnected-(X1AF-S-Pad38)") (class "Default")
      (node (ref "X1") (pin "38") (pinfunction "S_38") (pintype "passive"))
    )
    (net (code "70") (name "unconnected-(X1AI-S-Pad40)") (class "Default")
      (node (ref "X1") (pin "40") (pinfunction "S_40") (pintype "passive"))
    )
    (net (code "71") (name "unconnected-(X1AK-S-Pad42)") (class "Default")
      (node (ref "X1") (pin "42") (pinfunction "S_42") (pintype "passive"))
    )
    (net (code "72") (name "unconnected-(X1AM-S-Pad44)") (class "Default")
      (node (ref "X1") (pin "44") (pinfunction "S_44") (pintype "passive"))
    )
    (net (code "73") (name "unconnected-(X1AO-S-Pad46)") (class "Default")
      (node (ref "X1") (pin "46") (pinfunction "S_46") (pintype "passive"))
    )
    (net (code "74") (name "unconnected-(X1AQ-S-Pad48)") (class "Default")
      (node (ref "X1") (pin "48") (pinfunction "S_48") (pintype "passive"))
    )
    (net (code "75") (name "unconnected-(X1AS-S-Pad5)") (class "Default")
      (node (ref "X1") (pin "5") (pinfunction "S_5") (pintype "passive"))
    )
    (net (code "76") (name "unconnected-(X1AW-S-Pad6)") (class "Default")
      (node (ref "X1") (pin "6") (pinfunction "S_6") (pintype "passive"))
    )
    (net (code "77") (name "unconnected-(X1AX-S-Pad7)") (class "Default")
      (node (ref "X1") (pin "7") (pinfunction "S_7") (pintype "passive"))
    )
    (net (code "78") (name "unconnected-(X1AY-S-Pad8)") (class "Default")
      (node (ref "X1") (pin "8") (pinfunction "S_8") (pintype "passive"))
    )
    (net (code "79") (name "unconnected-(X1B-S-Pad10)") (class "Default")
      (node (ref "X1") (pin "10") (pinfunction "S_10") (pintype "passive"))
    )
    (net (code "80") (name "unconnected-(X1C-S-Pad11)") (class "Default")
      (node (ref "X1") (pin "11") (pinfunction "S_11") (pintype "passive"))
    )
    (net (code "81") (name "unconnected-(X1D-S-Pad12)") (class "Default")
      (node (ref "X1") (pin "12") (pinfunction "S_12") (pintype "passive"))
    )
    (net (code "82") (name "unconnected-(X1E-S-Pad13)") (class "Default")
      (node (ref "X1") (pin "13") (pinfunction "S_13") (pintype "passive"))
    )
    (net (code "83") (name "unconnected-(X1F-S-Pad14)") (class "Default")
      (node (ref "X1") (pin "14") (pinfunction "S_14") (pintype "passive"))
    )
    (net (code "84") (name "unconnected-(X1H-S-Pad16)") (class "Default")
      (node (ref "X1") (pin "16") (pinfunction "S_16") (pintype "passive"))
    )
    (net (code "85") (name "unconnected-(X1K-S-Pad19)") (class "Default")
      (node (ref "X1") (pin "19") (pinfunction "S_19") (pintype "passive"))
    )
    (net (code "86") (name "unconnected-(X1M-S-Pad20)") (class "Default")
      (node (ref "X1") (pin "20") (pinfunction "S_20") (pintype "passive"))
    )
    (net (code "87") (name "unconnected-(X1P-S-Pad23)") (class "Default")
      (node (ref "X1") (pin "23") (pinfunction "S_23") (pintype "passive"))
    )
    (net (code "88") (name "unconnected-(X1R-S-Pad25)") (class "Default")
      (node (ref "X1") (pin "25") (pinfunction "S_25") (pintype "passive"))
    )
    (net (code "89") (name "unconnected-(X1U-S-Pad28)") (class "Default")
      (node (ref "X1") (pin "28") (pinfunction "S_28") (pintype "passive"))
    )
    (net (code "90") (name "unconnected-(X1W-S-Pad3)") (class "Default")
      (node (ref "X1") (pin "3") (pinfunction "S_3") (pintype "passive"))
    )
    (net (code "91") (name "unconnected-(X1X-S-Pad30)") (class "Default")
      (node (ref "X1") (pin "30") (pinfunction "S_30") (pintype "passive"))
    )
    (net (code "92") (name "unconnected-(X1Z-S-Pad32)") (class "Default")
      (node (ref "X1") (pin "32") (pinfunction "S_32") (pintype "passive"))
    )
  )
)
